# CNEPuckRevF_Drivers_1.net
KiCad netlist of a schematic drawn in Altium Designer
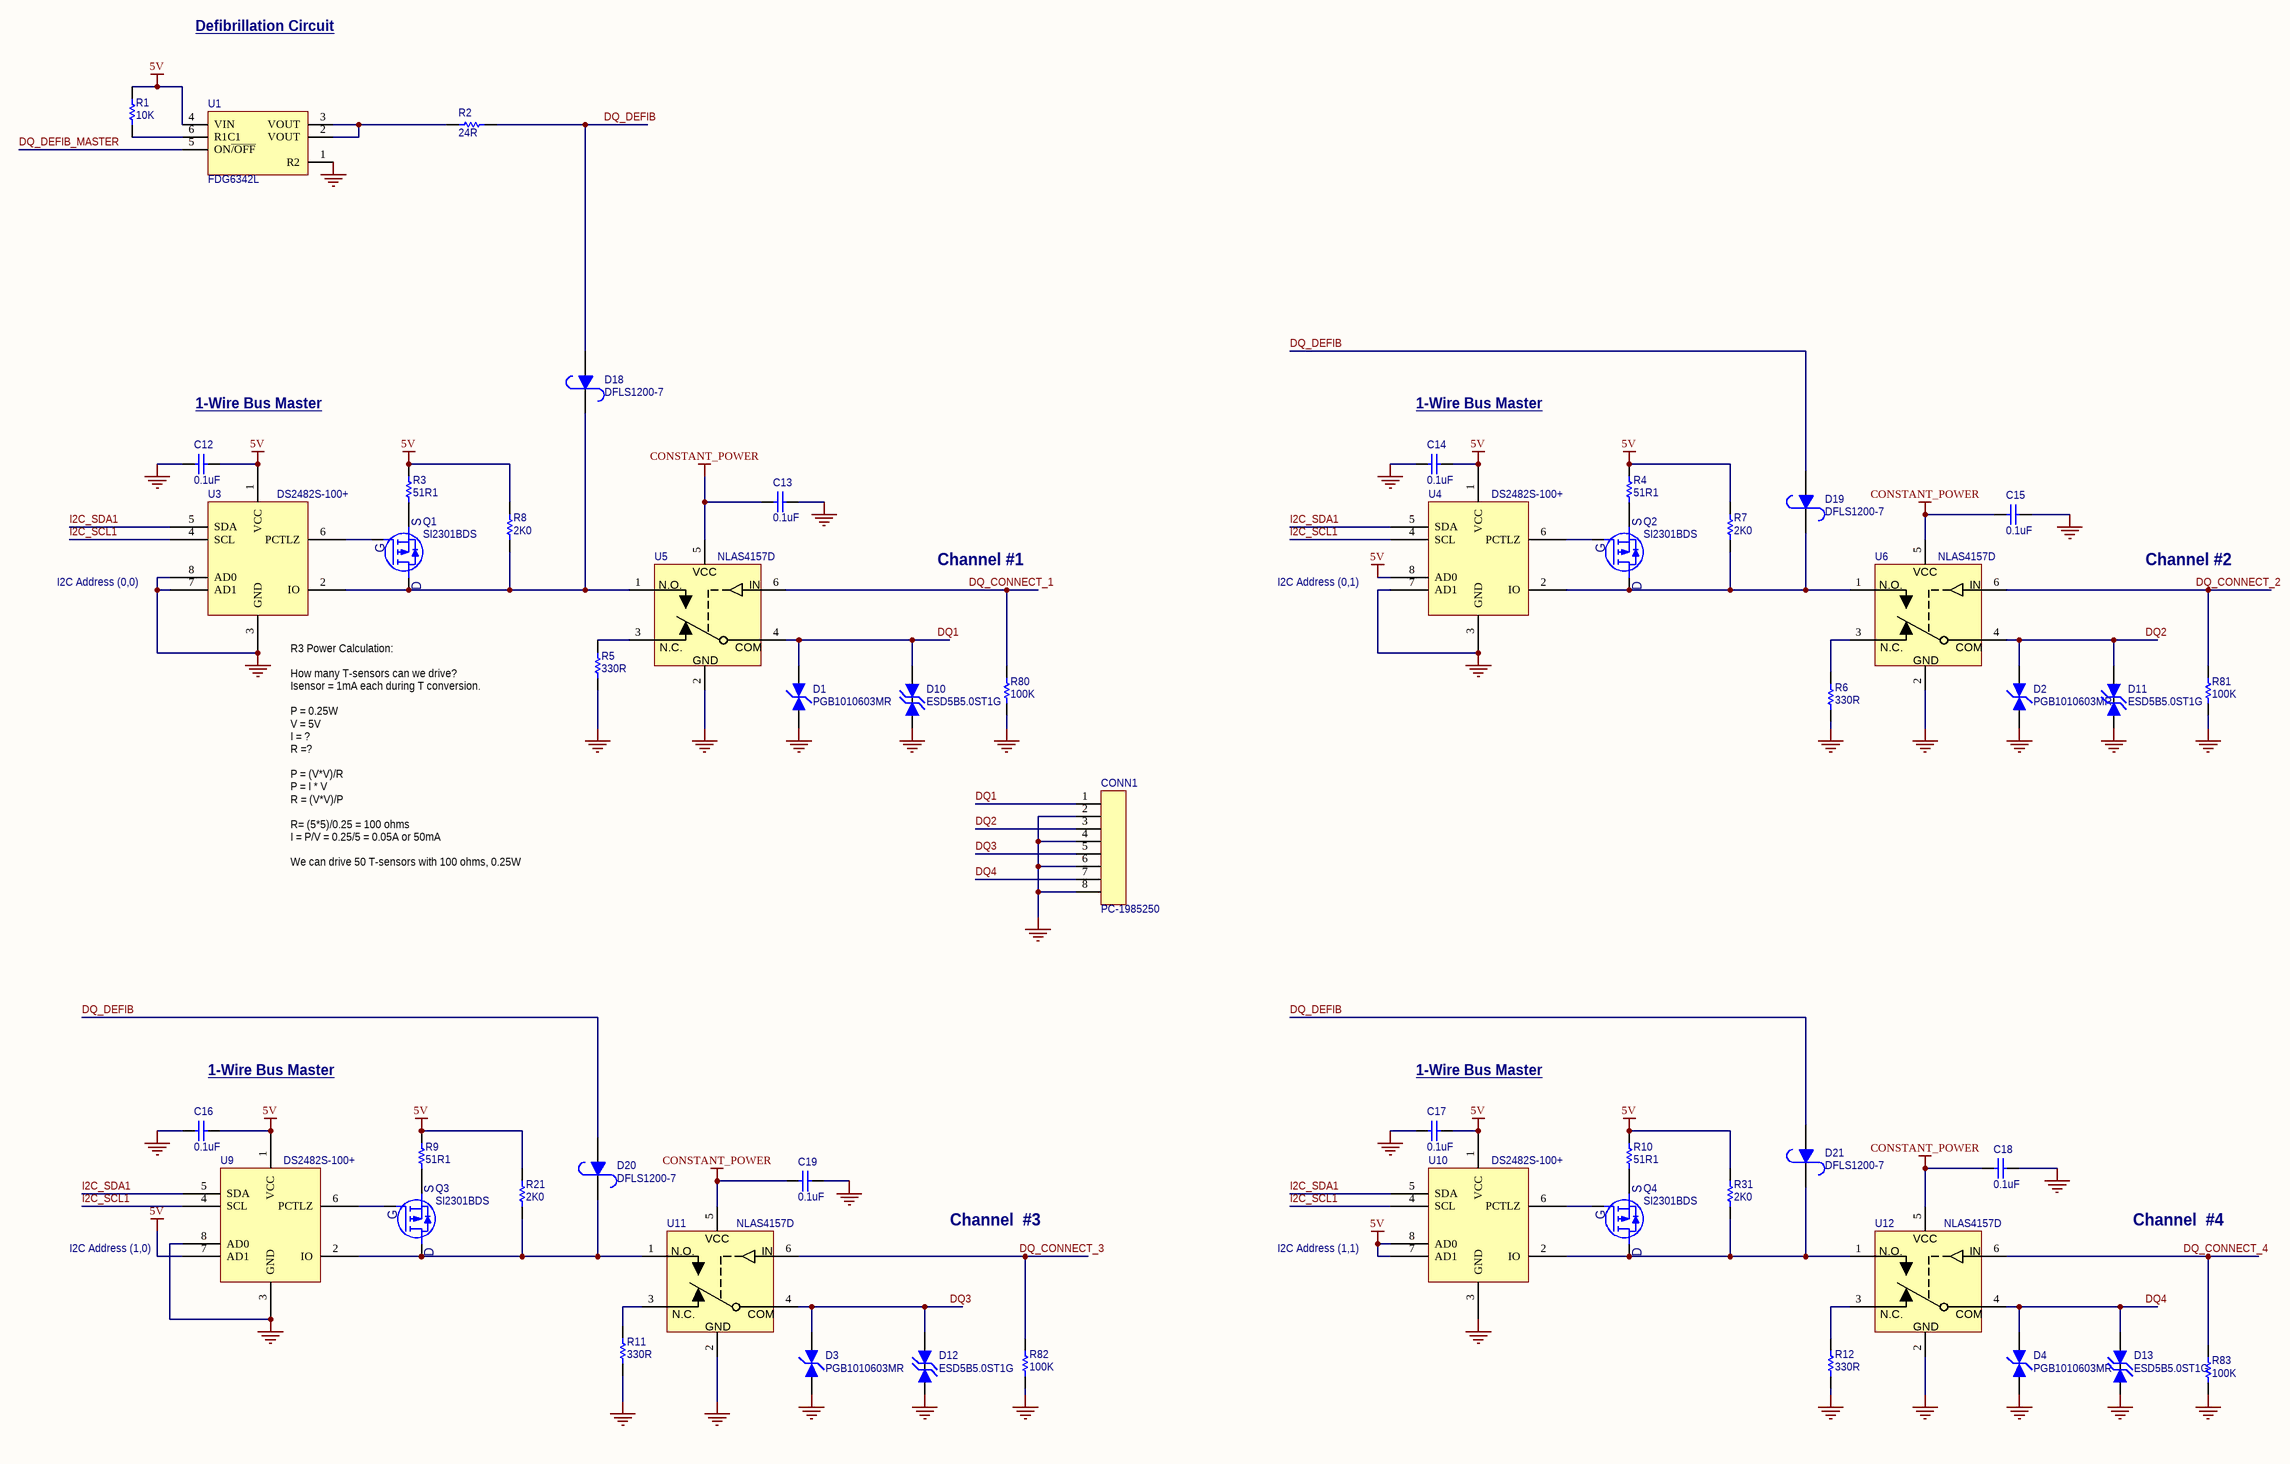
[diagram p0: CNEPuckRevF_Drivers_1.SchDoc]

(export (version "E")
  (design (tool "Eeschema 10.0.6"))
  (components
    (comp (ref "C12")
      (value "0.1uF")
      (footprint "RC0603")
      (description "CAP CERM .1UF 10% 16V X7R 0603")
      (fields (field (name "TOLERANCE") "±10%") (field (name "MANUFACTURER PART NUMBER") "0603YC104KAT2A"))
      (libsource (lib "Swage") (part "0603YC104KAT2A"))
    )
    (comp (ref "C13")
      (value "0.1uF")
      (footprint "RC0603")
      (description "CAP CERM .1UF 10% 16V X7R 0603")
      (fields (field (name "TOLERANCE") "±10%") (field (name "MANUFACTURER PART NUMBER") "0603YC104KAT2A"))
      (libsource (lib "Swage") (part "0603YC104KAT2A"))
    )
    (comp (ref "C14")
      (value "0.1uF")
      (footprint "RC0603")
      (description "CAP CERM .1UF 10% 16V X7R 0603")
      (fields (field (name "TOLERANCE") "±10%") (field (name "MANUFACTURER PART NUMBER") "0603YC104KAT2A"))
      (libsource (lib "Swage") (part "0603YC104KAT2A"))
    )
    (comp (ref "C15")
      (value "0.1uF")
      (footprint "RC0603")
      (description "CAP CERM .1UF 10% 16V X7R 0603")
      (fields (field (name "TOLERANCE") "±10%") (field (name "MANUFACTURER PART NUMBER") "0603YC104KAT2A"))
      (libsource (lib "Swage") (part "0603YC104KAT2A"))
    )
    (comp (ref "C16")
      (value "0.1uF")
      (footprint "RC0603")
      (description "CAP CERM .1UF 10% 16V X7R 0603")
      (fields (field (name "TOLERANCE") "±10%") (field (name "MANUFACTURER PART NUMBER") "0603YC104KAT2A"))
      (libsource (lib "Swage") (part "0603YC104KAT2A"))
    )
    (comp (ref "C17")
      (value "0.1uF")
      (footprint "RC0603")
      (description "CAP CERM .1UF 10% 16V X7R 0603")
      (fields (field (name "TOLERANCE") "±10%") (field (name "MANUFACTURER PART NUMBER") "0603YC104KAT2A"))
      (libsource (lib "Swage") (part "0603YC104KAT2A"))
    )
    (comp (ref "C18")
      (value "0.1uF")
      (footprint "RC0603")
      (description "CAP CERM .1UF 10% 16V X7R 0603")
      (fields (field (name "TOLERANCE") "±10%") (field (name "MANUFACTURER PART NUMBER") "0603YC104KAT2A"))
      (libsource (lib "Swage") (part "0603YC104KAT2A"))
    )
    (comp (ref "C19")
      (value "0.1uF")
      (footprint "RC0603")
      (description "CAP CERM .1UF 10% 16V X7R 0603")
      (fields (field (name "TOLERANCE") "±10%") (field (name "MANUFACTURER PART NUMBER") "0603YC104KAT2A"))
      (libsource (lib "Swage") (part "0603YC104KAT2A"))
    )
    (comp (ref "CONN1")
      (value "PC-1985250")
      (footprint "PTSA1.5/8-3.5-Z")
      (description "TERM BLOCK PCB 8POS 3.5MM GREEN")
      (fields
        (field (name "MANUFACTURER") "Phoenix Contact")
        (field (name "MANUFACTURER PART NUMBER") "1985250")
      )
      (libsource (lib "Swage") (part "1985250"))
    )
    (comp (ref "D1")
      (value "PGB1010603MR")
      (footprint "RC0603")
      (description "SUPPRESSOR ESD 24VDC 0603 SMD")
      (fields (field (name "MANUFACTURER") "Littelfuse Inc"))
      (libsource (lib "Swage") (part "PGB1010603MR"))
    )
    (comp (ref "D2")
      (value "PGB1010603MR")
      (footprint "RC0603")
      (description "SUPPRESSOR ESD 24VDC 0603 SMD")
      (fields (field (name "MANUFACTURER") "Littelfuse Inc"))
      (libsource (lib "Swage") (part "PGB1010603MR"))
    )
    (comp (ref "D3")
      (value "PGB1010603MR")
      (footprint "RC0603")
      (description "SUPPRESSOR ESD 24VDC 0603 SMD")
      (fields (field (name "MANUFACTURER") "Littelfuse Inc"))
      (libsource (lib "Swage") (part "PGB1010603MR"))
    )
    (comp (ref "D4")
      (value "PGB1010603MR")
      (footprint "RC0603")
      (description "SUPPRESSOR ESD 24VDC 0603 SMD")
      (fields (field (name "MANUFACTURER") "Littelfuse Inc"))
      (libsource (lib "Swage") (part "PGB1010603MR"))
    )
    (comp (ref "D10")
      (value "ESD5B5.0ST1G")
      (footprint "SOD-523")
      (description "TVS BIDIRECT 50W SOD523")
      (fields (field (name "MANUFACTURER") "ON Semiconductor"))
      (libsource (lib "Swage") (part "ESD5B5.0ST1G"))
    )
    (comp (ref "D11")
      (value "ESD5B5.0ST1G")
      (footprint "SOD-523")
      (description "TVS BIDIRECT 50W SOD523")
      (fields (field (name "MANUFACTURER") "ON Semiconductor"))
      (libsource (lib "Swage") (part "ESD5B5.0ST1G"))
    )
    (comp (ref "D12")
      (value "ESD5B5.0ST1G")
      (footprint "SOD-523")
      (description "TVS BIDIRECT 50W SOD523")
      (fields (field (name "MANUFACTURER") "ON Semiconductor"))
      (libsource (lib "Swage") (part "ESD5B5.0ST1G"))
    )
    (comp (ref "D13")
      (value "ESD5B5.0ST1G")
      (footprint "SOD-523")
      (description "TVS BIDIRECT 50W SOD523")
      (fields (field (name "MANUFACTURER") "ON Semiconductor"))
      (libsource (lib "Swage") (part "ESD5B5.0ST1G"))
    )
    (comp (ref "D18")
      (value "DFLS1200-7")
      (footprint "POWERDI-123")
      (description "DIODE SCHOTTKY 1A 200V PWRDI 123")
      (fields (field (name "MANUFACTURER") "Diodes Inc"))
      (libsource (lib "Swage") (part "DFLS1200-7"))
    )
    (comp (ref "D19")
      (value "DFLS1200-7")
      (footprint "POWERDI-123")
      (description "DIODE SCHOTTKY 1A 200V PWRDI 123")
      (fields (field (name "MANUFACTURER") "Diodes Inc"))
      (libsource (lib "Swage") (part "DFLS1200-7"))
    )
    (comp (ref "D20")
      (value "DFLS1200-7")
      (footprint "POWERDI-123")
      (description "DIODE SCHOTTKY 1A 200V PWRDI 123")
      (fields (field (name "MANUFACTURER") "Diodes Inc"))
      (libsource (lib "Swage") (part "DFLS1200-7"))
    )
    (comp (ref "D21")
      (value "DFLS1200-7")
      (footprint "POWERDI-123")
      (description "DIODE SCHOTTKY 1A 200V PWRDI 123")
      (fields (field (name "MANUFACTURER") "Diodes Inc"))
      (libsource (lib "Swage") (part "DFLS1200-7"))
    )
    (comp (ref "Q1")
      (value "SI2301BDS")
      (footprint "SOT23(DGS)")
      (description "MOSFET P-CH 20V 2.2A SOT23-3")
      (fields
        (field (name "MANUFACTURER") "Vishay/Siliconix")
        (field (name "MANUFACTURER PART NUMBER") "SI2301BDS-T1-E3")
      )
      (libsource (lib "Swage") (part "SI2301BDS-T1-E3"))
    )
    (comp (ref "Q2")
      (value "SI2301BDS")
      (footprint "SOT23(DGS)")
      (description "MOSFET P-CH 20V 2.2A SOT23-3")
      (fields
        (field (name "MANUFACTURER") "Vishay/Siliconix")
        (field (name "MANUFACTURER PART NUMBER") "SI2301BDS-T1-E3")
      )
      (libsource (lib "Swage") (part "SI2301BDS-T1-E3"))
    )
    (comp (ref "Q3")
      (value "SI2301BDS")
      (footprint "SOT23(DGS)")
      (description "MOSFET P-CH 20V 2.2A SOT23-3")
      (fields
        (field (name "MANUFACTURER") "Vishay/Siliconix")
        (field (name "MANUFACTURER PART NUMBER") "SI2301BDS-T1-E3")
      )
      (libsource (lib "Swage") (part "SI2301BDS-T1-E3"))
    )
    (comp (ref "Q4")
      (value "SI2301BDS")
      (footprint "SOT23(DGS)")
      (description "MOSFET P-CH 20V 2.2A SOT23-3")
      (fields
        (field (name "MANUFACTURER") "Vishay/Siliconix")
        (field (name "MANUFACTURER PART NUMBER") "SI2301BDS-T1-E3")
      )
      (libsource (lib "Swage") (part "SI2301BDS-T1-E3"))
    )
    (comp (ref "R1")
      (value "10K")
      (footprint "RC0603")
      (description "RES 10K OHM 1/10W 5% 0603 SMD")
      (fields
        (field (name "MANUFACTURER") "Panasonic Electronic Components")
        (field (name "MANUFACTURER PART NUMBER") "ERJ-3GEYJ103V")
      )
      (libsource (lib "Swage") (part "ERJ-3GEYJ103V"))
    )
    (comp (ref "R2")
      (value "24R")
      (footprint "RES2512")
      (description "RES 24 OHM 1W 5% 2512 SMD")
      (fields
        (field (name "MANUFACTURER") "Vishay/Dale")
        (field (name "MANUFACTURER PART NUMBER") "CRCW251224R0JNEG")
      )
      (libsource (lib "Swage") (part "RMCF2512JT24R0"))
    )
    (comp (ref "R3")
      (value "51R1")
      (footprint "RC0603")
      (description "RES 51.1 OHM .25W 1% 0603 SMD")
      (fields
        (field (name "MANUFACTURER") "Vishay Dale")
        (field (name "MANUFACTURER PART NUMBER") "CRCW060351R1FKEAHP")
      )
      (libsource (lib "Swage") (part "CRCW060351R1FKEAHP"))
    )
    (comp (ref "R4")
      (value "51R1")
      (footprint "RC0603")
      (description "RES 51.1 OHM .25W 1% 0603 SMD")
      (fields
        (field (name "MANUFACTURER") "Vishay Dale")
        (field (name "MANUFACTURER PART NUMBER") "CRCW060351R1FKEAHP")
      )
      (libsource (lib "Swage") (part "CRCW060351R1FKEAHP"))
    )
    (comp (ref "R5")
      (value "330R")
      (footprint "RC0805")
      (description "RES 330 OHM 1/8W 5% 0805 SMD")
      (fields
        (field (name "MANUFACTURER") "KOA Speer Technologies")
        (field (name "MANUFACTURER PART NUMBER") "RK73B2ATTD331J")
      )
      (libsource (lib "Swage") (part "ERJ-6GEYJ331V"))
    )
    (comp (ref "R6")
      (value "330R")
      (footprint "RC0805")
      (description "RES 330 OHM 1/8W 5% 0805 SMD")
      (fields
        (field (name "MANUFACTURER") "KOA Speer Technologies")
        (field (name "MANUFACTURER PART NUMBER") "RK73B2ATTD331J")
      )
      (libsource (lib "Swage") (part "ERJ-6GEYJ331V"))
    )
    (comp (ref "R7")
      (value "2K0")
      (footprint "RC0603")
      (description "RES 2K OHM 1/10W 1% 0603 SMD")
      (fields
        (field (name "MANUFACTURER") "Panasonic Electronic Components")
        (field (name "MANUFACTURER PART NUMBER") "ERJ-3EKF2001V")
      )
      (libsource (lib "Swage") (part "ERJ-3EKF2001V"))
    )
    (comp (ref "R8")
      (value "2K0")
      (footprint "RC0603")
      (description "RES 2K OHM 1/10W 1% 0603 SMD")
      (fields
        (field (name "MANUFACTURER") "Panasonic Electronic Components")
        (field (name "MANUFACTURER PART NUMBER") "ERJ-3EKF2001V")
      )
      (libsource (lib "Swage") (part "ERJ-3EKF2001V"))
    )
    (comp (ref "R9")
      (value "51R1")
      (footprint "RC0603")
      (description "RES 51.1 OHM .25W 1% 0603 SMD")
      (fields
        (field (name "MANUFACTURER") "Vishay Dale")
        (field (name "MANUFACTURER PART NUMBER") "CRCW060351R1FKEAHP")
      )
      (libsource (lib "Swage") (part "CRCW060351R1FKEAHP"))
    )
    (comp (ref "R10")
      (value "51R1")
      (footprint "RC0603")
      (description "RES 51.1 OHM .25W 1% 0603 SMD")
      (fields
        (field (name "MANUFACTURER") "Vishay Dale")
        (field (name "MANUFACTURER PART NUMBER") "CRCW060351R1FKEAHP")
      )
      (libsource (lib "Swage") (part "CRCW060351R1FKEAHP"))
    )
    (comp (ref "R11")
      (value "330R")
      (footprint "RC0805")
      (description "RES 330 OHM 1/8W 5% 0805 SMD")
      (fields
        (field (name "MANUFACTURER") "KOA Speer Technologies")
        (field (name "MANUFACTURER PART NUMBER") "RK73B2ATTD331J")
      )
      (libsource (lib "Swage") (part "ERJ-6GEYJ331V"))
    )
    (comp (ref "R12")
      (value "330R")
      (footprint "RC0805")
      (description "RES 330 OHM 1/8W 5% 0805 SMD")
      (fields
        (field (name "MANUFACTURER") "KOA Speer Technologies")
        (field (name "MANUFACTURER PART NUMBER") "RK73B2ATTD331J")
      )
      (libsource (lib "Swage") (part "ERJ-6GEYJ331V"))
    )
    (comp (ref "R21")
      (value "2K0")
      (footprint "RC0603")
      (description "RES 2K OHM 1/10W 1% 0603 SMD")
      (fields
        (field (name "MANUFACTURER") "Panasonic Electronic Components")
        (field (name "MANUFACTURER PART NUMBER") "ERJ-3EKF2001V")
      )
      (libsource (lib "Swage") (part "ERJ-3EKF2001V"))
    )
    (comp (ref "R31")
      (value "2K0")
      (footprint "RC0603")
      (description "RES 2K OHM 1/10W 1% 0603 SMD")
      (fields
        (field (name "MANUFACTURER") "Panasonic Electronic Components")
        (field (name "MANUFACTURER PART NUMBER") "ERJ-3EKF2001V")
      )
      (libsource (lib "Swage") (part "ERJ-3EKF2001V"))
    )
    (comp (ref "R80")
      (value "100K")
      (footprint "RC0603")
      (description "RES 100K OHM 1/10W 5% 0603 SMD")
      (fields
        (field (name "MANUFACTURER") "Panasonic Electronic Components")
        (field (name "MANUFACTURER PART NUMBER") "ERJ-3GEYJ104V")
      )
      (libsource (lib "Swage") (part "ERJ-3GEYJ104V"))
    )
    (comp (ref "R81")
      (value "100K")
      (footprint "RC0603")
      (description "RES 100K OHM 1/10W 5% 0603 SMD")
      (fields
        (field (name "MANUFACTURER") "Panasonic Electronic Components")
        (field (name "MANUFACTURER PART NUMBER") "ERJ-3GEYJ104V")
      )
      (libsource (lib "Swage") (part "ERJ-3GEYJ104V"))
    )
    (comp (ref "R82")
      (value "100K")
      (footprint "RC0603")
      (description "RES 100K OHM 1/10W 5% 0603 SMD")
      (fields
        (field (name "MANUFACTURER") "Panasonic Electronic Components")
        (field (name "MANUFACTURER PART NUMBER") "ERJ-3GEYJ104V")
      )
      (libsource (lib "Swage") (part "ERJ-3GEYJ104V"))
    )
    (comp (ref "R83")
      (value "100K")
      (footprint "RC0603")
      (description "RES 100K OHM 1/10W 5% 0603 SMD")
      (fields
        (field (name "MANUFACTURER") "Panasonic Electronic Components")
        (field (name "MANUFACTURER PART NUMBER") "ERJ-3GEYJ104V")
      )
      (libsource (lib "Swage") (part "ERJ-3GEYJ104V"))
    )
    (comp (ref "U1")
      (value "FDG6342L")
      (footprint "TS5A3160")
      (description "IC LOAD SWITCH INTEGRATED SC70-6")
      (fields (field (name "MANUFACTURER") "Fairchild Semiconductor"))
      (libsource (lib "Swage") (part "FDG6342L"))
    )
    (comp (ref "U3")
      (value "DS2482S-100+")
      (footprint "SOIC127P580X153-8N")
      (description "IC BRIDGE I2C TO 1-WIRE 8-SOIC")
      (fields (field (name "MANUFACTURER") "Maxim Integrated"))
      (libsource (lib "Swage") (part "DS2482S-100+"))
    )
    (comp (ref "U4")
      (value "DS2482S-100+")
      (footprint "SOIC127P580X153-8N")
      (description "IC BRIDGE I2C TO 1-WIRE 8-SOIC")
      (fields (field (name "MANUFACTURER") "Maxim Integrated"))
      (libsource (lib "Swage") (part "DS2482S-100+"))
    )
    (comp (ref "U5")
      (value "NLAS4157D")
      (footprint "TS5A3160")
      (description "IC SWITCH SPDT SC88")
      (fields
        (field (name "MANUFACTURER") "ON Semiconductor")
        (field (name "MANUFACTURER PART NUMBER") "NLAS4157DFT2G")
      )
      (libsource (lib "Swage") (part "NLAS4157DFT2G"))
    )
    (comp (ref "U6")
      (value "NLAS4157D")
      (footprint "TS5A3160")
      (description "IC SWITCH SPDT SC88")
      (fields
        (field (name "MANUFACTURER") "ON Semiconductor")
        (field (name "MANUFACTURER PART NUMBER") "NLAS4157DFT2G")
      )
      (libsource (lib "Swage") (part "NLAS4157DFT2G"))
    )
    (comp (ref "U9")
      (value "DS2482S-100+")
      (footprint "SOIC127P580X153-8N")
      (description "IC BRIDGE I2C TO 1-WIRE 8-SOIC")
      (fields (field (name "MANUFACTURER") "Maxim Integrated"))
      (libsource (lib "Swage") (part "DS2482S-100+"))
    )
    (comp (ref "U10")
      (value "DS2482S-100+")
      (footprint "SOIC127P580X153-8N")
      (description "IC BRIDGE I2C TO 1-WIRE 8-SOIC")
      (fields (field (name "MANUFACTURER") "Maxim Integrated"))
      (libsource (lib "Swage") (part "DS2482S-100+"))
    )
    (comp (ref "U11")
      (value "NLAS4157D")
      (footprint "TS5A3160")
      (description "IC SWITCH SPDT SC88")
      (fields
        (field (name "MANUFACTURER") "ON Semiconductor")
        (field (name "MANUFACTURER PART NUMBER") "NLAS4157DFT2G")
      )
      (libsource (lib "Swage") (part "NLAS4157DFT2G"))
    )
    (comp (ref "U12")
      (value "NLAS4157D")
      (footprint "TS5A3160")
      (description "IC SWITCH SPDT SC88")
      (fields
        (field (name "MANUFACTURER") "ON Semiconductor")
        (field (name "MANUFACTURER PART NUMBER") "NLAS4157DFT2G")
      )
      (libsource (lib "Swage") (part "NLAS4157DFT2G"))
    )
  )
  (nets
    (net (code "1") (name "/DQ1") (class "Default")
      (node (ref "CONN1") (pin "1") (pinfunction "1_1") (pintype "passive"))
      (node (ref "D1") (pin "2") (pinfunction "2_2") (pintype "passive"))
      (node (ref "D10") (pin "2") (pinfunction "2_2") (pintype "passive"))
      (node (ref "U5") (pin "4") (pinfunction "4_4") (pintype "passive"))
    )
    (net (code "2") (name "/DQ2") (class "Default")
      (node (ref "CONN1") (pin "3") (pinfunction "3_3") (pintype "passive"))
      (node (ref "D11") (pin "2") (pinfunction "2_2") (pintype "passive"))
      (node (ref "D2") (pin "2") (pinfunction "2_2") (pintype "passive"))
      (node (ref "U6") (pin "4") (pinfunction "4_4") (pintype "passive"))
    )
    (net (code "3") (name "/DQ3") (class "Default")
      (node (ref "CONN1") (pin "5") (pinfunction "5_5") (pintype "passive"))
      (node (ref "D12") (pin "2") (pinfunction "2_2") (pintype "passive"))
      (node (ref "D3") (pin "2") (pinfunction "2_2") (pintype "passive"))
      (node (ref "U11") (pin "4") (pinfunction "4_4") (pintype "passive"))
    )
    (net (code "4") (name "/DQ4") (class "Default")
      (node (ref "CONN1") (pin "7") (pinfunction "7_7") (pintype "passive"))
      (node (ref "D13") (pin "2") (pinfunction "2_2") (pintype "passive"))
      (node (ref "D4") (pin "2") (pinfunction "2_2") (pintype "passive"))
      (node (ref "U12") (pin "4") (pinfunction "4_4") (pintype "passive"))
    )
    (net (code "5") (name "/DQ_CONNECT_1") (class "Default")
      (node (ref "R80") (pin "1") (pinfunction "1_1") (pintype "passive"))
      (node (ref "U5") (pin "6") (pinfunction "6_6") (pintype "passive"))
    )
    (net (code "6") (name "/DQ_CONNECT_2") (class "Default")
      (node (ref "R81") (pin "1") (pinfunction "1_1") (pintype "passive"))
      (node (ref "U6") (pin "6") (pinfunction "6_6") (pintype "passive"))
    )
    (net (code "7") (name "/DQ_CONNECT_3") (class "Default")
      (node (ref "R82") (pin "1") (pinfunction "1_1") (pintype "passive"))
      (node (ref "U11") (pin "6") (pinfunction "6_6") (pintype "passive"))
    )
    (net (code "8") (name "/DQ_CONNECT_4") (class "Default")
      (node (ref "R83") (pin "1") (pinfunction "1_1") (pintype "passive"))
      (node (ref "U12") (pin "6") (pinfunction "6_6") (pintype "passive"))
    )
    (net (code "9") (name "/DQ_DEFIB") (class "Default")
      (node (ref "D18") (pin "1") (pinfunction "A_1") (pintype "passive"))
      (node (ref "D19") (pin "1") (pinfunction "A_1") (pintype "passive"))
      (node (ref "D20") (pin "1") (pinfunction "A_1") (pintype "passive"))
      (node (ref "D21") (pin "1") (pinfunction "A_1") (pintype "passive"))
      (node (ref "R2") (pin "2") (pinfunction "2_2") (pintype "passive"))
    )
    (net (code "10") (name "/DQ_DEFIB_MASTER") (class "Default")
      (node (ref "U1") (pin "5") (pinfunction "ON~{/OFF}_5") (pintype "passive"))
    )
    (net (code "11") (name "/I2C_SCL1") (class "Default")
      (node (ref "U10") (pin "4") (pinfunction "SCL_4") (pintype "passive"))
      (node (ref "U3") (pin "4") (pinfunction "SCL_4") (pintype "passive"))
      (node (ref "U4") (pin "4") (pinfunction "SCL_4") (pintype "passive"))
      (node (ref "U9") (pin "4") (pinfunction "SCL_4") (pintype "passive"))
    )
    (net (code "12") (name "/I2C_SDA1") (class "Default")
      (node (ref "U10") (pin "5") (pinfunction "SDA_5") (pintype "passive"))
      (node (ref "U3") (pin "5") (pinfunction "SDA_5") (pintype "passive"))
      (node (ref "U4") (pin "5") (pinfunction "SDA_5") (pintype "passive"))
      (node (ref "U9") (pin "5") (pinfunction "SDA_5") (pintype "passive"))
    )
    (net (code "13") (name "5V") (class "Default")
      (node (ref "C12") (pin "2") (pinfunction "2_2") (pintype "passive"))
      (node (ref "C14") (pin "2") (pinfunction "2_2") (pintype "passive"))
      (node (ref "C16") (pin "2") (pinfunction "2_2") (pintype "passive"))
      (node (ref "C17") (pin "2") (pinfunction "2_2") (pintype "passive"))
      (node (ref "R1") (pin "1") (pinfunction "1_1") (pintype "passive"))
      (node (ref "R10") (pin "1") (pinfunction "1_1") (pintype "passive"))
      (node (ref "R21") (pin "1") (pinfunction "1_1") (pintype "passive"))
      (node (ref "R3") (pin "1") (pinfunction "1_1") (pintype "passive"))
      (node (ref "R31") (pin "1") (pinfunction "1_1") (pintype "passive"))
      (node (ref "R4") (pin "1") (pinfunction "1_1") (pintype "passive"))
      (node (ref "R7") (pin "1") (pinfunction "1_1") (pintype "passive"))
      (node (ref "R8") (pin "1") (pinfunction "1_1") (pintype "passive"))
      (node (ref "R9") (pin "1") (pinfunction "1_1") (pintype "passive"))
      (node (ref "U1") (pin "4") (pinfunction "VIN_4") (pintype "passive"))
      (node (ref "U10") (pin "1") (pinfunction "VCC_1") (pintype "passive"))
      (node (ref "U10") (pin "7") (pinfunction "AD1_7") (pintype "passive"))
      (node (ref "U10") (pin "8") (pinfunction "AD0_8") (pintype "passive"))
      (node (ref "U3") (pin "1") (pinfunction "VCC_1") (pintype "passive"))
      (node (ref "U4") (pin "1") (pinfunction "VCC_1") (pintype "passive"))
      (node (ref "U4") (pin "8") (pinfunction "AD0_8") (pintype "passive"))
      (node (ref "U9") (pin "1") (pinfunction "VCC_1") (pintype "passive"))
      (node (ref "U9") (pin "7") (pinfunction "AD1_7") (pintype "passive"))
    )
    (net (code "14") (name "CONSTANT_POWER") (class "Default")
      (node (ref "C13") (pin "1") (pinfunction "1_1") (pintype "passive"))
      (node (ref "C15") (pin "1") (pinfunction "1_1") (pintype "passive"))
      (node (ref "C18") (pin "1") (pinfunction "1_1") (pintype "passive"))
      (node (ref "C19") (pin "1") (pinfunction "1_1") (pintype "passive"))
      (node (ref "U11") (pin "5") (pinfunction "5_5") (pintype "passive"))
      (node (ref "U12") (pin "5") (pinfunction "5_5") (pintype "passive"))
      (node (ref "U5") (pin "5") (pinfunction "5_5") (pintype "passive"))
      (node (ref "U6") (pin "5") (pinfunction "5_5") (pintype "passive"))
    )
    (net (code "15") (name "GND") (class "Default")
      (node (ref "C12") (pin "1") (pinfunction "1_1") (pintype "passive"))
      (node (ref "C13") (pin "2") (pinfunction "2_2") (pintype "passive"))
      (node (ref "C14") (pin "1") (pinfunction "1_1") (pintype "passive"))
      (node (ref "C15") (pin "2") (pinfunction "2_2") (pintype "passive"))
      (node (ref "C16") (pin "1") (pinfunction "1_1") (pintype "passive"))
      (node (ref "C17") (pin "1") (pinfunction "1_1") (pintype "passive"))
      (node (ref "C18") (pin "2") (pinfunction "2_2") (pintype "passive"))
      (node (ref "C19") (pin "2") (pinfunction "2_2") (pintype "passive"))
      (node (ref "CONN1") (pin "2") (pinfunction "2_2") (pintype "passive"))
      (node (ref "CONN1") (pin "4") (pinfunction "4_4") (pintype "passive"))
      (node (ref "CONN1") (pin "6") (pinfunction "6_6") (pintype "passive"))
      (node (ref "CONN1") (pin "8") (pinfunction "8_8") (pintype "passive"))
      (node (ref "D1") (pin "1") (pintype "passive"))
      (node (ref "D10") (pin "1") (pintype "passive"))
      (node (ref "D11") (pin "1") (pintype "passive"))
      (node (ref "D12") (pin "1") (pintype "passive"))
      (node (ref "D13") (pin "1") (pintype "passive"))
      (node (ref "D2") (pin "1") (pintype "passive"))
      (node (ref "D3") (pin "1") (pintype "passive"))
      (node (ref "D4") (pin "1") (pintype "passive"))
      (node (ref "R11") (pin "2") (pinfunction "2_2") (pintype "passive"))
      (node (ref "R12") (pin "2") (pinfunction "2_2") (pintype "passive"))
      (node (ref "R5") (pin "2") (pinfunction "2_2") (pintype "passive"))
      (node (ref "R6") (pin "2") (pinfunction "2_2") (pintype "passive"))
      (node (ref "R80") (pin "2") (pinfunction "2_2") (pintype "passive"))
      (node (ref "R81") (pin "2") (pinfunction "2_2") (pintype "passive"))
      (node (ref "R82") (pin "2") (pinfunction "2_2") (pintype "passive"))
      (node (ref "R83") (pin "2") (pinfunction "2_2") (pintype "passive"))
      (node (ref "U1") (pin "1") (pinfunction "R2_1") (pintype "passive"))
      (node (ref "U10") (pin "3") (pinfunction "GND_3") (pintype "passive"))
      (node (ref "U11") (pin "2") (pinfunction "GND_2") (pintype "passive"))
      (node (ref "U12") (pin "2") (pinfunction "GND_2") (pintype "passive"))
      (node (ref "U3") (pin "3") (pinfunction "GND_3") (pintype "passive"))
      (node (ref "U3") (pin "7") (pinfunction "AD1_7") (pintype "passive"))
      (node (ref "U3") (pin "8") (pinfunction "AD0_8") (pintype "passive"))
      (node (ref "U4") (pin "3") (pinfunction "GND_3") (pintype "passive"))
      (node (ref "U4") (pin "7") (pinfunction "AD1_7") (pintype "passive"))
      (node (ref "U5") (pin "2") (pinfunction "GND_2") (pintype "passive"))
      (node (ref "U6") (pin "2") (pinfunction "GND_2") (pintype "passive"))
      (node (ref "U9") (pin "3") (pinfunction "GND_3") (pintype "passive"))
      (node (ref "U9") (pin "8") (pinfunction "AD0_8") (pintype "passive"))
    )
    (net (code "16") (name "Net-(D18-K)") (class "Default")
      (node (ref "D18") (pin "2") (pinfunction "K_2") (pintype "passive"))
      (node (ref "Q1") (pin "D") (pinfunction "D_D") (pintype "passive"))
      (node (ref "R8") (pin "2") (pinfunction "2_2") (pintype "passive"))
      (node (ref "U3") (pin "2") (pinfunction "IO_2") (pintype "passive"))
      (node (ref "U5") (pin "1") (pinfunction "NO_1") (pintype "passive"))
    )
    (net (code "17") (name "Net-(D19-K)") (class "Default")
      (node (ref "D19") (pin "2") (pinfunction "K_2") (pintype "passive"))
      (node (ref "Q2") (pin "D") (pinfunction "D_D") (pintype "passive"))
      (node (ref "R7") (pin "2") (pinfunction "2_2") (pintype "passive"))
      (node (ref "U4") (pin "2") (pinfunction "IO_2") (pintype "passive"))
      (node (ref "U6") (pin "1") (pinfunction "NO_1") (pintype "passive"))
    )
    (net (code "18") (name "Net-(D20-K)") (class "Default")
      (node (ref "D20") (pin "2") (pinfunction "K_2") (pintype "passive"))
      (node (ref "Q3") (pin "D") (pinfunction "D_D") (pintype "passive"))
      (node (ref "R21") (pin "2") (pinfunction "2_2") (pintype "passive"))
      (node (ref "U11") (pin "1") (pinfunction "NO_1") (pintype "passive"))
      (node (ref "U9") (pin "2") (pinfunction "IO_2") (pintype "passive"))
    )
    (net (code "19") (name "Net-(D21-K)") (class "Default")
      (node (ref "D21") (pin "2") (pinfunction "K_2") (pintype "passive"))
      (node (ref "Q4") (pin "D") (pinfunction "D_D") (pintype "passive"))
      (node (ref "R31") (pin "2") (pinfunction "2_2") (pintype "passive"))
      (node (ref "U10") (pin "2") (pinfunction "IO_2") (pintype "passive"))
      (node (ref "U12") (pin "1") (pinfunction "NO_1") (pintype "passive"))
    )
    (net (code "20") (name "Net-(Q1-PadS)") (class "Default")
      (node (ref "Q1") (pin "S") (pinfunction "S_S") (pintype "passive"))
      (node (ref "R3") (pin "2") (pinfunction "2_2") (pintype "passive"))
    )
    (net (code "21") (name "Net-(Q2-PadS)") (class "Default")
      (node (ref "Q2") (pin "S") (pinfunction "S_S") (pintype "passive"))
      (node (ref "R4") (pin "2") (pinfunction "2_2") (pintype "passive"))
    )
    (net (code "22") (name "Net-(Q3-PadS)") (class "Default")
      (node (ref "Q3") (pin "S") (pinfunction "S_S") (pintype "passive"))
      (node (ref "R9") (pin "2") (pinfunction "2_2") (pintype "passive"))
    )
    (net (code "23") (name "Net-(Q4-PadS)") (class "Default")
      (node (ref "Q4") (pin "S") (pinfunction "S_S") (pintype "passive"))
      (node (ref "R10") (pin "2") (pinfunction "2_2") (pintype "passive"))
    )
    (net (code "24") (name "Net-(R2-Pad1)") (class "Default")
      (node (ref "R2") (pin "1") (pinfunction "1_1") (pintype "passive"))
      (node (ref "U1") (pin "2") (pinfunction "VOUT_2") (pintype "passive"))
      (node (ref "U1") (pin "3") (pinfunction "VOUT_3") (pintype "passive"))
    )
    (net (code "25") (name "Net-(U1-R1C1)") (class "Default")
      (node (ref "R1") (pin "2") (pinfunction "2_2") (pintype "passive"))
      (node (ref "U1") (pin "6") (pinfunction "R1C1_6") (pintype "passive"))
    )
    (net (code "26") (name "Net-(U3-PCTLZ)") (class "Default")
      (node (ref "Q1") (pin "G") (pinfunction "G_G") (pintype "passive"))
      (node (ref "U3") (pin "6") (pinfunction "PCTLZ_6") (pintype "passive"))
    )
    (net (code "27") (name "Net-(U4-PCTLZ)") (class "Default")
      (node (ref "Q2") (pin "G") (pinfunction "G_G") (pintype "passive"))
      (node (ref "U4") (pin "6") (pinfunction "PCTLZ_6") (pintype "passive"))
    )
    (net (code "28") (name "Net-(U5-NC)") (class "Default")
      (node (ref "R5") (pin "1") (pinfunction "1_1") (pintype "passive"))
      (node (ref "U5") (pin "3") (pinfunction "NC_3") (pintype "passive"))
    )
    (net (code "29") (name "Net-(U6-NC)") (class "Default")
      (node (ref "R6") (pin "1") (pinfunction "1_1") (pintype "passive"))
      (node (ref "U6") (pin "3") (pinfunction "NC_3") (pintype "passive"))
    )
    (net (code "30") (name "Net-(U9-PCTLZ)") (class "Default")
      (node (ref "Q3") (pin "G") (pinfunction "G_G") (pintype "passive"))
      (node (ref "U9") (pin "6") (pinfunction "PCTLZ_6") (pintype "passive"))
    )
    (net (code "31") (name "Net-(U10-PCTLZ)") (class "Default")
      (node (ref "Q4") (pin "G") (pinfunction "G_G") (pintype "passive"))
      (node (ref "U10") (pin "6") (pinfunction "PCTLZ_6") (pintype "passive"))
    )
    (net (code "32") (name "Net-(U11-NC)") (class "Default")
      (node (ref "R11") (pin "1") (pinfunction "1_1") (pintype "passive"))
      (node (ref "U11") (pin "3") (pinfunction "NC_3") (pintype "passive"))
    )
    (net (code "33") (name "Net-(U12-NC)") (class "Default")
      (node (ref "R12") (pin "1") (pinfunction "1_1") (pintype "passive"))
      (node (ref "U12") (pin "3") (pinfunction "NC_3") (pintype "passive"))
    )
  )
)
